# I2C_Breakout.net
KiCad netlist of a schematic drawn in Altium Designer
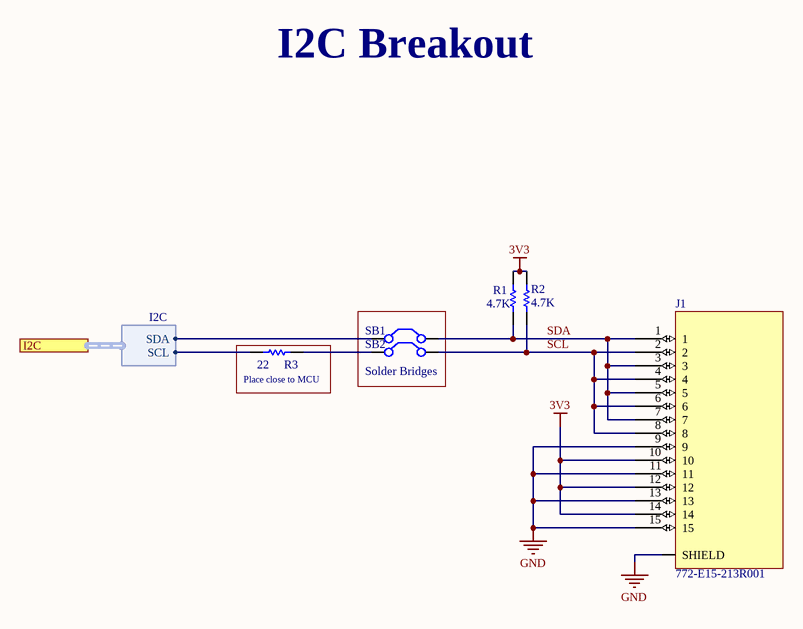
[diagram p0: I2C_Breakout.SchDoc]

(export (version "E")
  (design (tool "Eeschema 10.0.6"))
  (components
    (comp (ref "J1")
      (value "772-E15-213R001")
      (footprint "LaunchyRIOFootprints:15-Pos D-Sub")
      (description "15-Position Connector")
      (fields (field (name "DIGIKEY PART NUMBER") "NOR1010-ND"))
      (libsource (lib "LaunchyRIOComponents") (part "15-Position Connector"))
    )
    (comp (ref "R1")
      (value "4.7K")
      (footprint "0402")
      (description "Resistor")
      (fields (field (name "Comment") "Res1"))
      (libsource (lib "Miscellaneous Devices") (part "Res1"))
    )
    (comp (ref "R2")
      (value "4.7K")
      (footprint "0402")
      (description "Resistor")
      (fields (field (name "Comment") "Res1"))
      (libsource (lib "Miscellaneous Devices") (part "Res1"))
    )
    (comp (ref "R3")
      (value "22")
      (footprint "0402")
      (description "Resistor")
      (fields (field (name "Comment") "Res1"))
      (libsource (lib "Miscellaneous Devices") (part "Res1"))
    )
    (comp (ref "SB1")
      (value "Solder Bridge")
      (footprint "SB-2pos")
      (description "Jumper Wire")
      (libsource (lib "Miscellaneous Devices") (part "Jumper"))
    )
    (comp (ref "SB2")
      (value "Solder Bridge")
      (footprint "SB-2pos")
      (description "Jumper Wire")
      (libsource (lib "Miscellaneous Devices") (part "Jumper"))
    )
  )
  (nets
    (net (code "2") (name "/SCL") (class "Default")
      (node (ref "J1") (pin "2") (pinfunction "2_2") (pintype "bidirectional"))
      (node (ref "J1") (pin "4") (pinfunction "4_4") (pintype "bidirectional"))
      (node (ref "J1") (pin "6") (pinfunction "6_6") (pintype "bidirectional"))
      (node (ref "J1") (pin "8") (pinfunction "8_8") (pintype "bidirectional"))
      (node (ref "R2") (pin "1") (pinfunction "1_1") (pintype "passive"))
      (node (ref "SB2") (pin "2") (pinfunction "C2_2") (pintype "passive"))
    )
    (net (code "3") (name "/SDA") (class "Default")
      (node (ref "J1") (pin "1") (pinfunction "1_1") (pintype "bidirectional"))
      (node (ref "J1") (pin "3") (pinfunction "3_3") (pintype "bidirectional"))
      (node (ref "J1") (pin "5") (pinfunction "5_5") (pintype "bidirectional"))
      (node (ref "J1") (pin "7") (pinfunction "7_7") (pintype "bidirectional"))
      (node (ref "R1") (pin "1") (pinfunction "1_1") (pintype "passive"))
      (node (ref "SB1") (pin "2") (pinfunction "C2_2") (pintype "passive"))
    )
    (net (code "5") (name "3V3") (class "Default")
      (node (ref "J1") (pin "10") (pinfunction "10_10") (pintype "bidirectional"))
      (node (ref "J1") (pin "12") (pinfunction "12_12") (pintype "bidirectional"))
      (node (ref "J1") (pin "14") (pinfunction "14_14") (pintype "bidirectional"))
      (node (ref "R1") (pin "2") (pinfunction "2_2") (pintype "passive"))
      (node (ref "R2") (pin "2") (pinfunction "2_2") (pintype "passive"))
    )
    (net (code "6") (name "GND") (class "Default")
      (node (ref "J1") (pin "11") (pinfunction "11_11") (pintype "bidirectional"))
      (node (ref "J1") (pin "13") (pinfunction "13_13") (pintype "bidirectional"))
      (node (ref "J1") (pin "15") (pinfunction "15_15") (pintype "bidirectional"))
      (node (ref "J1") (pin "9") (pinfunction "9_9") (pintype "bidirectional"))
      (node (ref "J1") (pin "SHIELD") (pinfunction "SHIELD_SHIELD") (pintype "passive"))
    )
    (net (code "7") (name "Net-(SB2-C1)") (class "Default")
      (node (ref "R3") (pin "2") (pinfunction "2_2") (pintype "passive"))
      (node (ref "SB2") (pin "1") (pinfunction "C1_1") (pintype "passive"))
    )
    (net (code "8") (name "unconnected-(R3-Pad1)") (class "Default")
      (node (ref "R3") (pin "1") (pinfunction "1_1") (pintype "passive"))
    )
    (net (code "9") (name "unconnected-(SB1-C1-Pad1)") (class "Default")
      (node (ref "SB1") (pin "1") (pinfunction "C1_1") (pintype "passive"))
    )
  )
)
